# SparkFun_6DoF_ISM330DHCX_Qwiic_Micro.net
KiCad netlist of a schematic drawn in EAGLE
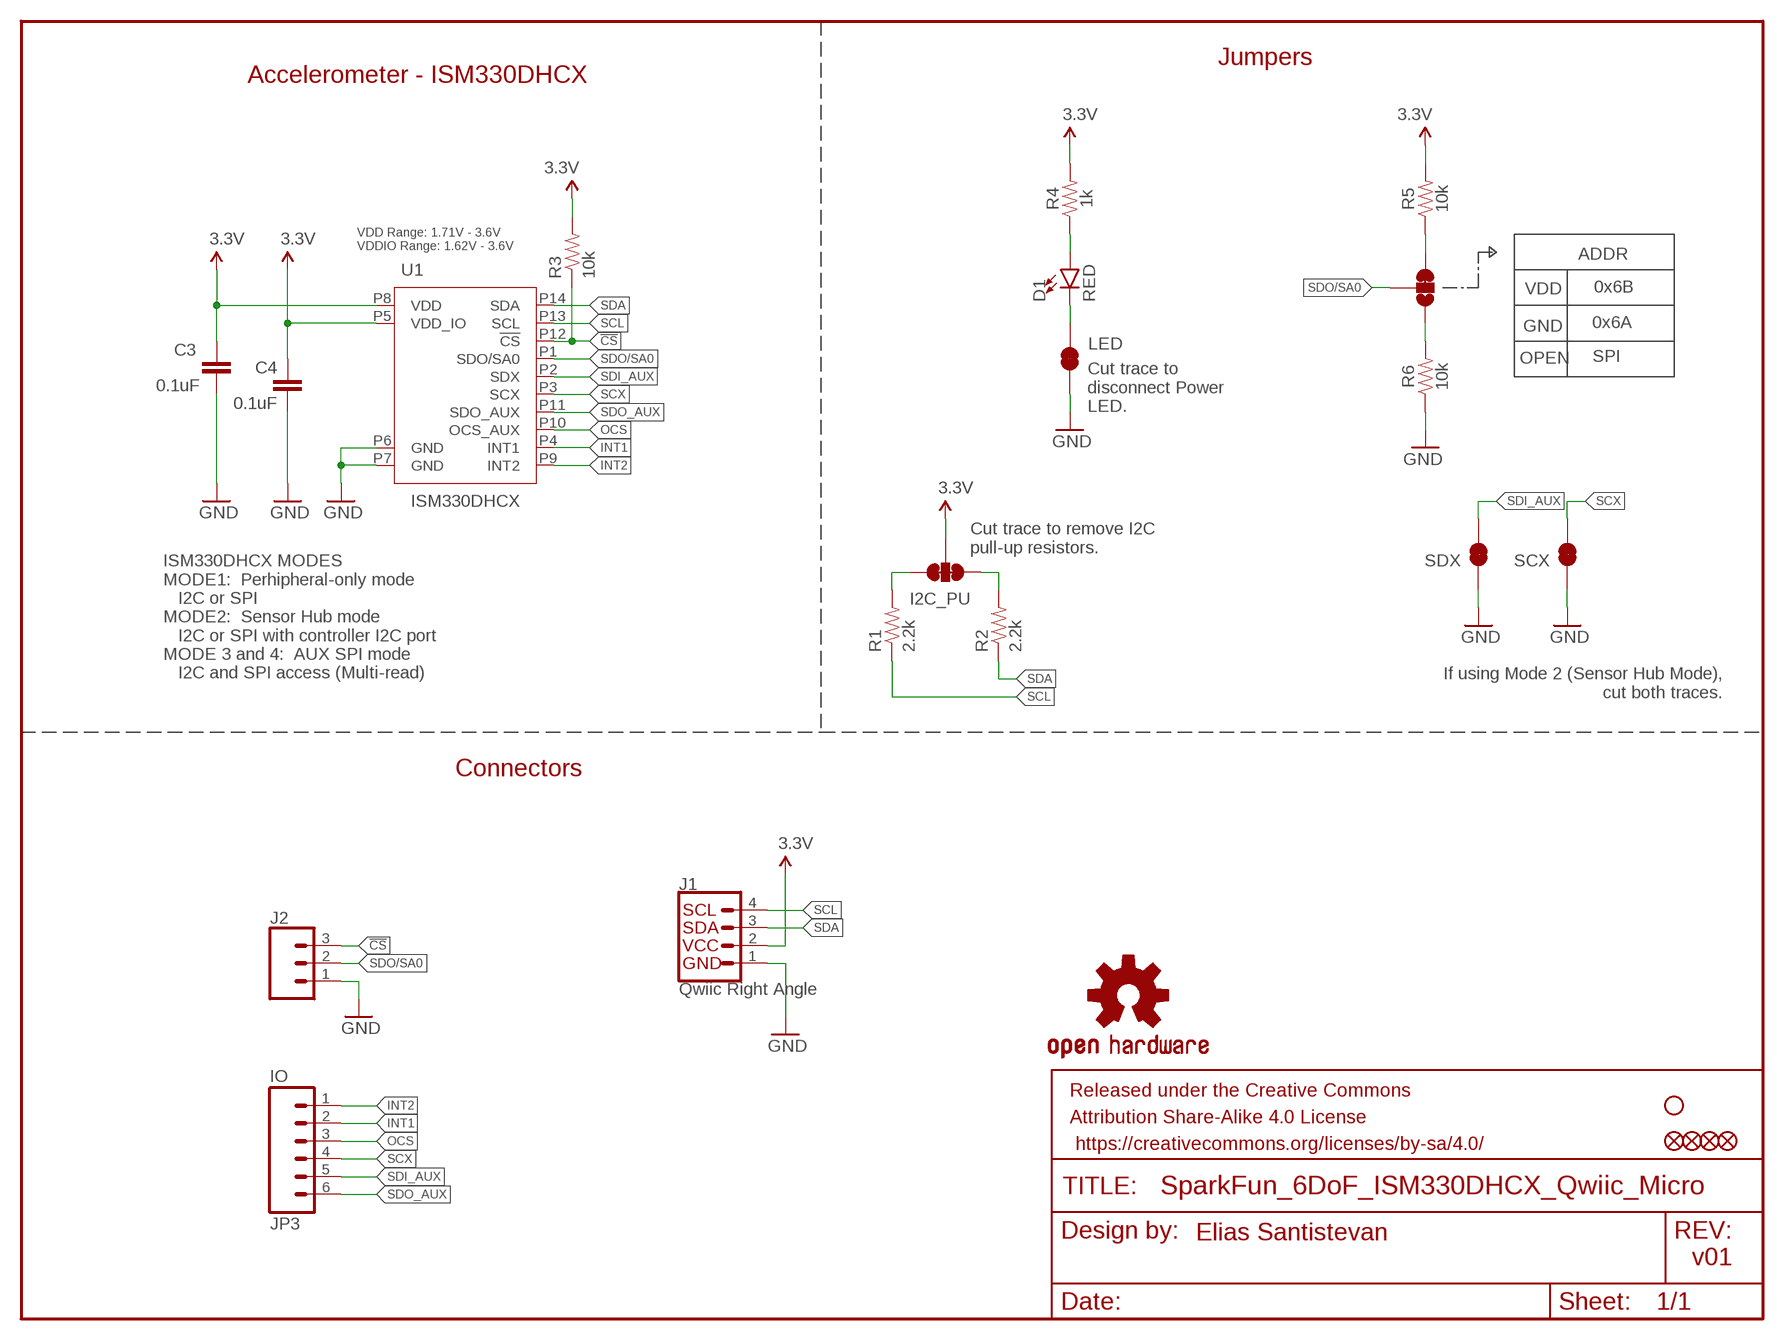
[diagram p0: schematic, sheet 1]

(export (version "E")
  (design (tool "Eeschema 10.0.6"))
  (components
    (comp (ref "ADDR")
      (value "JUMPER-SMT_3_1-NC_TRACE_SILK")
      (footprint "eagle-import:SMT-JUMPER_3_1-NC_TRACE_SILK")
      (libsource (lib "eagle-import") (part "JUMPER-SMT_3_1-NC_TRACE_SILK"))
    )
    (comp (ref "C3")
      (value "0.1uF")
      (footprint "eagle-import:0402-TIGHT")
      (libsource (lib "eagle-import") (part "0.1UF-0402T-6.3V-10%-X7R"))
    )
    (comp (ref "C4")
      (value "0.1uF")
      (footprint "eagle-import:0402-TIGHT")
      (libsource (lib "eagle-import") (part "0.1UF-0402T-6.3V-10%-X7R"))
    )
    (comp (ref "D1")
      (value "RED")
      (footprint "eagle-import:LED-0603")
      (libsource (lib "eagle-import") (part "LED-RED0603"))
    )
    (comp (ref "FD1")
      (value "FIDUCIALUFIDUCIAL")
      (footprint "eagle-import:FIDUCIAL-MICRO")
      (libsource (lib "eagle-import") (part "FIDUCIALUFIDUCIAL"))
    )
    (comp (ref "FD2")
      (value "FIDUCIALUFIDUCIAL")
      (footprint "eagle-import:FIDUCIAL-MICRO")
      (libsource (lib "eagle-import") (part "FIDUCIALUFIDUCIAL"))
    )
    (comp (ref "FID1")
      (value "FIDUCIALUFIDUCIAL")
      (footprint "eagle-import:FIDUCIAL-MICRO")
      (libsource (lib "eagle-import") (part "FIDUCIALUFIDUCIAL"))
    )
    (comp (ref "FID2")
      (value "FIDUCIALUFIDUCIAL")
      (footprint "eagle-import:FIDUCIAL-MICRO")
      (libsource (lib "eagle-import") (part "FIDUCIALUFIDUCIAL"))
    )
    (comp (ref "FRAME1")
      (value "FRAME-LETTER")
      (footprint "eagle-import:CREATIVE_COMMONS")
      (fields (field (name "DESIGNER") "Elias Santistevan"))
      (libsource (lib "eagle-import") (part "FRAME-LETTER"))
    )
    (comp (ref "I2C_PU")
      (value "S_MODE")
      (footprint "eagle-import:SMT-JUMPER_3_2-NC_TRACE_SILK")
      (libsource (lib "eagle-import") (part "JUMPER-SMT_3_2-NC_TRACE_SILK"))
    )
    (comp (ref "J1")
      (value "Qwiic Right Angle")
      (footprint "eagle-import:JST04_1MM_RA")
      (libsource (lib "eagle-import") (part "I2C_STANDARDQWIIC"))
    )
    (comp (ref "J2")
      (value "CONN_031X03_NO_SILK")
      (footprint "eagle-import:1X03_NO_SILK")
      (libsource (lib "eagle-import") (part "CONN_031X03_NO_SILK"))
    )
    (comp (ref "JP3")
      (value "IO")
      (footprint "eagle-import:1X06_NO_SILK")
      (libsource (lib "eagle-import") (part "CONN_06NO_SILK_NO_POP"))
    )
    (comp (ref "LED")
      (value "JUMPER-SMT_2_NC_TRACE_SILK")
      (footprint "eagle-import:SMT-JUMPER_2_NC_TRACE_SILK")
      (libsource (lib "eagle-import") (part "JUMPER-SMT_2_NC_TRACE_SILK"))
    )
    (comp (ref "LOGO2")
      (value "OSHW-LOGOMINI")
      (footprint "eagle-import:OSHW-LOGO-MINI")
      (libsource (lib "eagle-import") (part "OSHW-LOGOMINI"))
    )
    (comp (ref "R1")
      (value "2.2k")
      (footprint "eagle-import:0402-TIGHT")
      (libsource (lib "eagle-import") (part "2.2KOHM-0402T-1/16W-1%"))
    )
    (comp (ref "R2")
      (value "2.2k")
      (footprint "eagle-import:0402-TIGHT")
      (libsource (lib "eagle-import") (part "2.2KOHM-0402T-1/16W-1%"))
    )
    (comp (ref "R3")
      (value "10k")
      (footprint "eagle-import:0402-TIGHT")
      (libsource (lib "eagle-import") (part "10KOHM-0402T-1/16W-1%"))
    )
    (comp (ref "R4")
      (value "1k")
      (footprint "eagle-import:0402-TIGHT")
      (libsource (lib "eagle-import") (part "1KOHM-0402T-1/16W-1%"))
    )
    (comp (ref "R5")
      (value "10k")
      (footprint "eagle-import:0402-TIGHT")
      (libsource (lib "eagle-import") (part "10KOHM-0402T-1/16W-1%"))
    )
    (comp (ref "R6")
      (value "10k")
      (footprint "eagle-import:0402-TIGHT")
      (libsource (lib "eagle-import") (part "10KOHM-0402T-1/16W-1%"))
    )
    (comp (ref "SCX")
      (value "JUMPER-SMT_2_NC_TRACE_SILK")
      (footprint "eagle-import:SMT-JUMPER_2_NC_TRACE_SILK")
      (libsource (lib "eagle-import") (part "JUMPER-SMT_2_NC_TRACE_SILK"))
    )
    (comp (ref "SDX")
      (value "JUMPER-SMT_2_NC_TRACE_SILK")
      (footprint "eagle-import:SMT-JUMPER_2_NC_TRACE_SILK")
      (libsource (lib "eagle-import") (part "JUMPER-SMT_2_NC_TRACE_SILK"))
    )
    (comp (ref "STANDOFF1")
      (value "STAND-OFFTIGHT")
      (footprint "eagle-import:STAND-OFF-TIGHT")
      (libsource (lib "eagle-import") (part "STAND-OFFTIGHT"))
    )
    (comp (ref "U1")
      (value "ISM330DHCX")
      (footprint "eagle-import:LGA-14L")
      (libsource (lib "eagle-import") (part "ISM330DHCX"))
    )
  )
  (nets
    (net (code "1") (name "/~{CS}") (class "Default")
      (node (ref "J2") (pin "3") (pinfunction "3_3") (pintype "passive"))
      (node (ref "R3") (pin "1") (pinfunction "1_1") (pintype "passive"))
      (node (ref "U1") (pin "P12") (pinfunction "~{CS}_P12") (pintype "bidirectional"))
    )
    (net (code "2") (name "3.3V") (class "Default")
      (node (ref "C3") (pin "1") (pinfunction "1_1") (pintype "passive"))
      (node (ref "C4") (pin "1") (pinfunction "1_1") (pintype "passive"))
      (node (ref "I2C_PU") (pin "2") (pinfunction "2_2") (pintype "passive"))
      (node (ref "J1") (pin "2") (pinfunction "2_2") (pintype "power_in"))
      (node (ref "R3") (pin "2") (pinfunction "2_2") (pintype "passive"))
      (node (ref "R4") (pin "2") (pinfunction "2_2") (pintype "passive"))
      (node (ref "R5") (pin "2") (pinfunction "2_2") (pintype "passive"))
      (node (ref "U1") (pin "P5") (pinfunction "VDD_IO_P5") (pintype "power_in"))
      (node (ref "U1") (pin "P8") (pinfunction "VDD_P8") (pintype "power_in"))
    )
    (net (code "3") (name "GND") (class "Default")
      (node (ref "C3") (pin "2") (pinfunction "2_2") (pintype "passive"))
      (node (ref "C4") (pin "2") (pinfunction "2_2") (pintype "passive"))
      (node (ref "J1") (pin "1") (pinfunction "1_1") (pintype "power_in"))
      (node (ref "J2") (pin "1") (pinfunction "1_1") (pintype "passive"))
      (node (ref "LED") (pin "1") (pinfunction "1_1") (pintype "passive"))
      (node (ref "R6") (pin "1") (pinfunction "1_1") (pintype "passive"))
      (node (ref "SCX") (pin "1") (pinfunction "1_1") (pintype "passive"))
      (node (ref "SDX") (pin "1") (pinfunction "1_1") (pintype "passive"))
      (node (ref "U1") (pin "P6") (pinfunction "GND_P6") (pintype "power_in"))
      (node (ref "U1") (pin "P7") (pinfunction "GND_P7") (pintype "power_in"))
    )
    (net (code "4") (name "INT1") (class "Default")
      (node (ref "JP3") (pin "2") (pinfunction "2_2") (pintype "passive"))
      (node (ref "U1") (pin "P4") (pinfunction "INT1_P4") (pintype "bidirectional"))
    )
    (net (code "5") (name "INT2") (class "Default")
      (node (ref "JP3") (pin "1") (pinfunction "1_1") (pintype "passive"))
      (node (ref "U1") (pin "P9") (pinfunction "INT2_P9") (pintype "bidirectional"))
    )
    (net (code "6") (name "Net-(ADDR-Pad1)") (class "Default")
      (node (ref "ADDR") (pin "1") (pinfunction "1_1") (pintype "passive"))
      (node (ref "R6") (pin "2") (pinfunction "2_2") (pintype "passive"))
    )
    (net (code "7") (name "Net-(ADDR-Pad3)") (class "Default")
      (node (ref "ADDR") (pin "3") (pinfunction "3_3") (pintype "passive"))
      (node (ref "R5") (pin "1") (pinfunction "1_1") (pintype "passive"))
    )
    (net (code "8") (name "Net-(D1-PadA)") (class "Default")
      (node (ref "D1") (pin "A") (pinfunction "A_A") (pintype "passive"))
      (node (ref "R4") (pin "1") (pinfunction "1_1") (pintype "passive"))
    )
    (net (code "9") (name "Net-(D1-PadC)") (class "Default")
      (node (ref "D1") (pin "C") (pinfunction "C_C") (pintype "passive"))
      (node (ref "LED") (pin "2") (pinfunction "2_2") (pintype "passive"))
    )
    (net (code "10") (name "Net-(I2C_PU-Pad1)") (class "Default")
      (node (ref "I2C_PU") (pin "1") (pinfunction "1_1") (pintype "passive"))
      (node (ref "R1") (pin "2") (pinfunction "2_2") (pintype "passive"))
    )
    (net (code "11") (name "Net-(I2C_PU-Pad3)") (class "Default")
      (node (ref "I2C_PU") (pin "3") (pinfunction "3_3") (pintype "passive"))
      (node (ref "R2") (pin "2") (pinfunction "2_2") (pintype "passive"))
    )
    (net (code "12") (name "OCS") (class "Default")
      (node (ref "JP3") (pin "3") (pinfunction "3_3") (pintype "passive"))
      (node (ref "U1") (pin "P10") (pinfunction "OCS_AUX_P10") (pintype "bidirectional"))
    )
    (net (code "13") (name "SCL") (class "Default")
      (node (ref "J1") (pin "4") (pinfunction "4_4") (pintype "passive"))
      (node (ref "R1") (pin "1") (pinfunction "1_1") (pintype "passive"))
      (node (ref "U1") (pin "P13") (pinfunction "SCL_P13") (pintype "bidirectional"))
    )
    (net (code "14") (name "SCX") (class "Default")
      (node (ref "JP3") (pin "4") (pinfunction "4_4") (pintype "passive"))
      (node (ref "SCX") (pin "2") (pinfunction "2_2") (pintype "passive"))
      (node (ref "U1") (pin "P3") (pinfunction "SCX_P3") (pintype "bidirectional"))
    )
    (net (code "15") (name "SDA") (class "Default")
      (node (ref "J1") (pin "3") (pinfunction "3_3") (pintype "passive"))
      (node (ref "R2") (pin "1") (pinfunction "1_1") (pintype "passive"))
      (node (ref "U1") (pin "P14") (pinfunction "SDA_P14") (pintype "bidirectional"))
    )
    (net (code "16") (name "SDI_AUX") (class "Default")
      (node (ref "JP3") (pin "5") (pinfunction "5_5") (pintype "passive"))
      (node (ref "SDX") (pin "2") (pinfunction "2_2") (pintype "passive"))
      (node (ref "U1") (pin "P2") (pinfunction "SDX_P2") (pintype "bidirectional"))
    )
    (net (code "17") (name "SDO_AUX") (class "Default")
      (node (ref "JP3") (pin "6") (pinfunction "6_6") (pintype "passive"))
      (node (ref "U1") (pin "P11") (pinfunction "SDO_AUX_P11") (pintype "bidirectional"))
    )
    (net (code "18") (name "SDO{slash}SA0") (class "Default")
      (node (ref "ADDR") (pin "2") (pinfunction "2_2") (pintype "passive"))
      (node (ref "J2") (pin "2") (pinfunction "2_2") (pintype "passive"))
      (node (ref "U1") (pin "P1") (pinfunction "SDO/SA0_P1") (pintype "bidirectional"))
    )
  )
)
